# AntilogMM.net
KiCad netlist of a schematic drawn in EAGLE
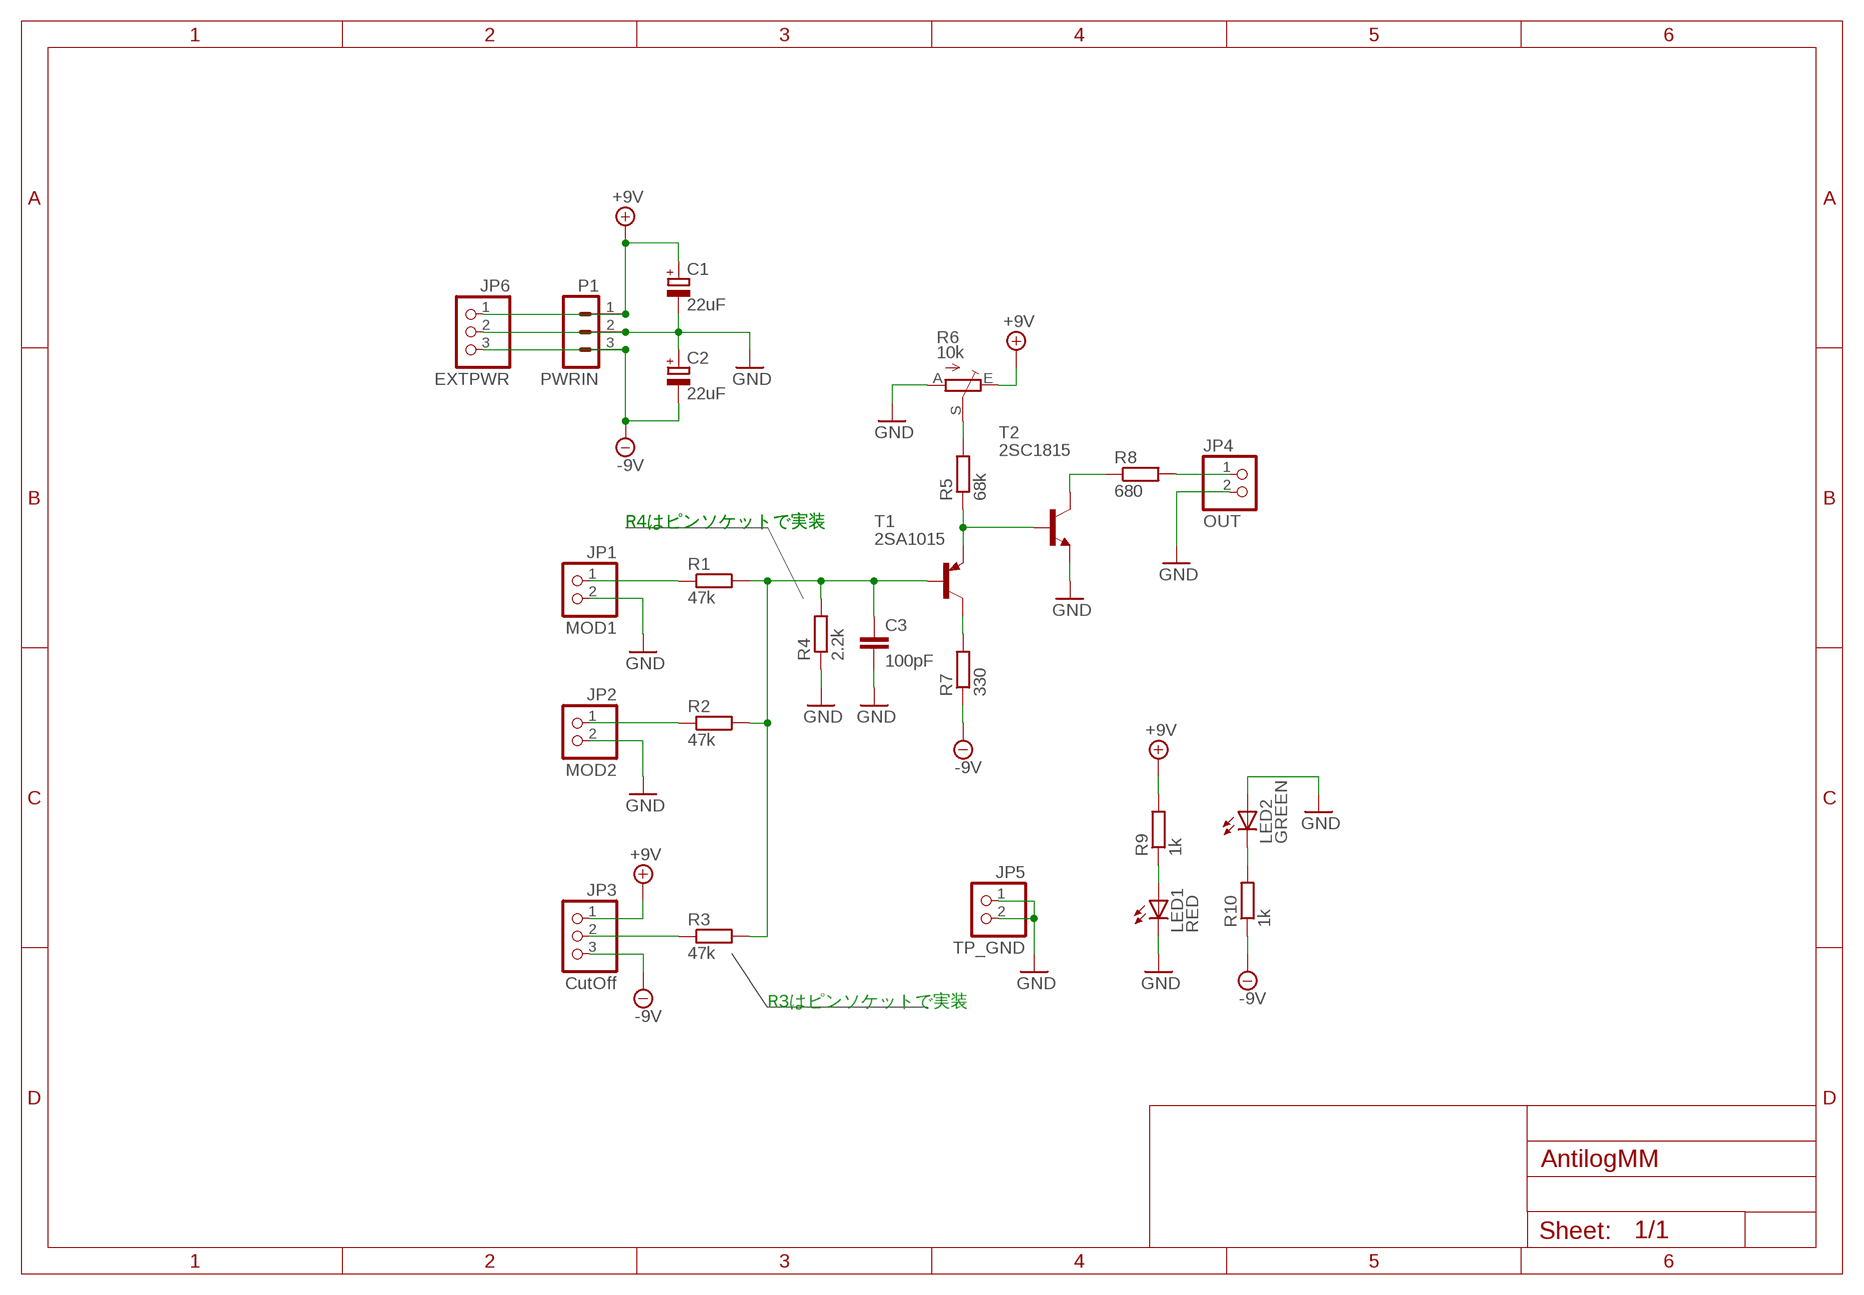
[diagram p0: schematic, sheet 1]

(export (version "E")
  (design (tool "Eeschema 10.0.6"))
  (components
    (comp (ref "C1")
      (value "22uF")
      (footprint "eagle-import:E2,5-6")
      (libsource (lib "eagle-import") (part "CPOL-EUE2.5-6"))
    )
    (comp (ref "C2")
      (value "22uF")
      (footprint "eagle-import:E2,5-6")
      (libsource (lib "eagle-import") (part "CPOL-EUE2.5-6"))
    )
    (comp (ref "C3")
      (value "100pF")
      (footprint "eagle-import:C050-024X044")
      (libsource (lib "eagle-import") (part "C-EU050-024X044"))
    )
    (comp (ref "JP1")
      (value "MOD1")
      (footprint "eagle-import:1X02")
      (libsource (lib "eagle-import") (part "PINHD-1X2"))
    )
    (comp (ref "JP2")
      (value "MOD2")
      (footprint "eagle-import:1X02")
      (libsource (lib "eagle-import") (part "PINHD-1X2"))
    )
    (comp (ref "JP3")
      (value "CutOff")
      (footprint "eagle-import:1X03")
      (libsource (lib "eagle-import") (part "PINHD-1X3"))
    )
    (comp (ref "JP4")
      (value "OUT")
      (footprint "eagle-import:1X02")
      (libsource (lib "eagle-import") (part "PINHD-1X2"))
    )
    (comp (ref "JP5")
      (value "TP_GND")
      (footprint "eagle-import:1X02")
      (libsource (lib "eagle-import") (part "PINHD-1X2"))
    )
    (comp (ref "JP6")
      (value "EXTPWR")
      (footprint "eagle-import:1X03")
      (libsource (lib "eagle-import") (part "PINHD-1X3"))
    )
    (comp (ref "LED1")
      (value "RED")
      (footprint "eagle-import:LED3MM")
      (libsource (lib "eagle-import") (part "LED3MM"))
    )
    (comp (ref "LED2")
      (value "GREEN")
      (footprint "eagle-import:LED3MM")
      (libsource (lib "eagle-import") (part "LED3MM"))
    )
    (comp (ref "P1")
      (value "PWRIN")
      (footprint "eagle-import:B3B-EH-A")
      (libsource (lib "eagle-import") (part "B3B-EH-A"))
    )
    (comp (ref "R1")
      (value "47k")
      (footprint "eagle-import:0207_7")
      (libsource (lib "eagle-import") (part "R-EU_0207/7"))
    )
    (comp (ref "R2")
      (value "47k")
      (footprint "eagle-import:0207_7")
      (libsource (lib "eagle-import") (part "R-EU_0207/7"))
    )
    (comp (ref "R3")
      (value "47k")
      (footprint "eagle-import:0207_7")
      (libsource (lib "eagle-import") (part "R-EU_0207/7"))
    )
    (comp (ref "R4")
      (value "2.2k")
      (footprint "eagle-import:0207_7")
      (libsource (lib "eagle-import") (part "R-EU_0207/7"))
    )
    (comp (ref "R5")
      (value "68k")
      (footprint "eagle-import:0207_7")
      (libsource (lib "eagle-import") (part "R-EU_0207/7"))
    )
    (comp (ref "R6")
      (value "10k")
      (footprint "eagle-import:B25P")
      (libsource (lib "eagle-import") (part "TRIM_EU-B25P"))
    )
    (comp (ref "R7")
      (value "330")
      (footprint "eagle-import:0207_7")
      (libsource (lib "eagle-import") (part "R-EU_0207/7"))
    )
    (comp (ref "R8")
      (value "680")
      (footprint "eagle-import:0207_7")
      (libsource (lib "eagle-import") (part "R-EU_0207/7"))
    )
    (comp (ref "R9")
      (value "1k")
      (footprint "eagle-import:0207_7")
      (libsource (lib "eagle-import") (part "R-EU_0207/7"))
    )
    (comp (ref "R10")
      (value "1k")
      (footprint "eagle-import:0207_7")
      (libsource (lib "eagle-import") (part "R-EU_0207/7"))
    )
    (comp (ref "T1")
      (value "2SA1015")
      (footprint "eagle-import:TO92-ECB")
      (libsource (lib "eagle-import") (part "-PNP-TO92-ECB"))
    )
    (comp (ref "T2")
      (value "2SC1815")
      (footprint "eagle-import:TO92-ECB")
      (libsource (lib "eagle-import") (part "-NPN-TO92-ECB"))
    )
  )
  (nets
    (net (code "1") (name "+9V") (class "Default")
      (node (ref "C1") (pin "+") (pinfunction "+_+") (pintype "passive"))
      (node (ref "JP3") (pin "1") (pinfunction "1_1") (pintype "passive"))
      (node (ref "JP6") (pin "1") (pinfunction "1_1") (pintype "passive"))
      (node (ref "P1") (pin "1") (pinfunction "1_1") (pintype "passive"))
      (node (ref "R6") (pin "E") (pinfunction "E_E") (pintype "passive"))
      (node (ref "R9") (pin "2") (pinfunction "2_2") (pintype "passive"))
    )
    (net (code "2") (name "-9V") (class "Default")
      (node (ref "C2") (pin "-") (pinfunction "-_-") (pintype "passive"))
      (node (ref "JP3") (pin "3") (pinfunction "3_3") (pintype "passive"))
      (node (ref "JP6") (pin "3") (pinfunction "3_3") (pintype "passive"))
      (node (ref "P1") (pin "3") (pinfunction "3_3") (pintype "passive"))
      (node (ref "R10") (pin "1") (pinfunction "1_1") (pintype "passive"))
      (node (ref "R7") (pin "1") (pinfunction "1_1") (pintype "passive"))
    )
    (net (code "3") (name "GND") (class "Default")
      (node (ref "C1") (pin "-") (pinfunction "-_-") (pintype "passive"))
      (node (ref "C2") (pin "+") (pinfunction "+_+") (pintype "passive"))
      (node (ref "C3") (pin "2") (pinfunction "2_2") (pintype "passive"))
      (node (ref "JP1") (pin "2") (pinfunction "2_2") (pintype "passive"))
      (node (ref "JP2") (pin "2") (pinfunction "2_2") (pintype "passive"))
      (node (ref "JP4") (pin "2") (pinfunction "2_2") (pintype "passive"))
      (node (ref "JP5") (pin "1") (pinfunction "1_1") (pintype "passive"))
      (node (ref "JP5") (pin "2") (pinfunction "2_2") (pintype "passive"))
      (node (ref "JP6") (pin "2") (pinfunction "2_2") (pintype "passive"))
      (node (ref "LED1") (pin "K") (pinfunction "C_K") (pintype "passive"))
      (node (ref "LED2") (pin "A") (pinfunction "A_A") (pintype "passive"))
      (node (ref "P1") (pin "2") (pinfunction "2_2") (pintype "passive"))
      (node (ref "R4") (pin "1") (pinfunction "1_1") (pintype "passive"))
      (node (ref "R6") (pin "A") (pinfunction "A_A") (pintype "passive"))
      (node (ref "T2") (pin "E") (pinfunction "E_E") (pintype "passive"))
    )
    (net (code "4") (name "Net-(C3-Pad1)") (class "Default")
      (node (ref "C3") (pin "1") (pinfunction "1_1") (pintype "passive"))
      (node (ref "R1") (pin "2") (pinfunction "2_2") (pintype "passive"))
      (node (ref "R2") (pin "2") (pinfunction "2_2") (pintype "passive"))
      (node (ref "R3") (pin "2") (pinfunction "2_2") (pintype "passive"))
      (node (ref "R4") (pin "2") (pinfunction "2_2") (pintype "passive"))
      (node (ref "T1") (pin "B") (pinfunction "B_B") (pintype "passive"))
    )
    (net (code "5") (name "Net-(JP1-Pad1)") (class "Default")
      (node (ref "JP1") (pin "1") (pinfunction "1_1") (pintype "passive"))
      (node (ref "R1") (pin "1") (pinfunction "1_1") (pintype "passive"))
    )
    (net (code "6") (name "Net-(JP2-Pad1)") (class "Default")
      (node (ref "JP2") (pin "1") (pinfunction "1_1") (pintype "passive"))
      (node (ref "R2") (pin "1") (pinfunction "1_1") (pintype "passive"))
    )
    (net (code "7") (name "Net-(JP3-Pad2)") (class "Default")
      (node (ref "JP3") (pin "2") (pinfunction "2_2") (pintype "passive"))
      (node (ref "R3") (pin "1") (pinfunction "1_1") (pintype "passive"))
    )
    (net (code "8") (name "Net-(JP4-Pad1)") (class "Default")
      (node (ref "JP4") (pin "1") (pinfunction "1_1") (pintype "passive"))
      (node (ref "R8") (pin "2") (pinfunction "2_2") (pintype "passive"))
    )
    (net (code "9") (name "Net-(LED1-PadA)") (class "Default")
      (node (ref "LED1") (pin "A") (pinfunction "A_A") (pintype "passive"))
      (node (ref "R9") (pin "1") (pinfunction "1_1") (pintype "passive"))
    )
    (net (code "10") (name "Net-(LED2-C)") (class "Default")
      (node (ref "LED2") (pin "K") (pinfunction "C_K") (pintype "passive"))
      (node (ref "R10") (pin "2") (pinfunction "2_2") (pintype "passive"))
    )
    (net (code "11") (name "Net-(R5-Pad1)") (class "Default")
      (node (ref "R5") (pin "1") (pinfunction "1_1") (pintype "passive"))
      (node (ref "T1") (pin "E") (pinfunction "E_E") (pintype "passive"))
      (node (ref "T2") (pin "B") (pinfunction "B_B") (pintype "passive"))
    )
    (net (code "12") (name "Net-(R5-Pad2)") (class "Default")
      (node (ref "R5") (pin "2") (pinfunction "2_2") (pintype "passive"))
      (node (ref "R6") (pin "S") (pinfunction "S_S") (pintype "passive"))
    )
    (net (code "13") (name "Net-(R7-Pad2)") (class "Default")
      (node (ref "R7") (pin "2") (pinfunction "2_2") (pintype "passive"))
      (node (ref "T1") (pin "C") (pinfunction "C_C") (pintype "passive"))
    )
    (net (code "14") (name "Net-(R8-Pad1)") (class "Default")
      (node (ref "R8") (pin "1") (pinfunction "1_1") (pintype "passive"))
      (node (ref "T2") (pin "C") (pinfunction "C_C") (pintype "passive"))
    )
  )
)
